# CM_ETHERNET.net
KiCad netlist of a schematic drawn in Altium Designer
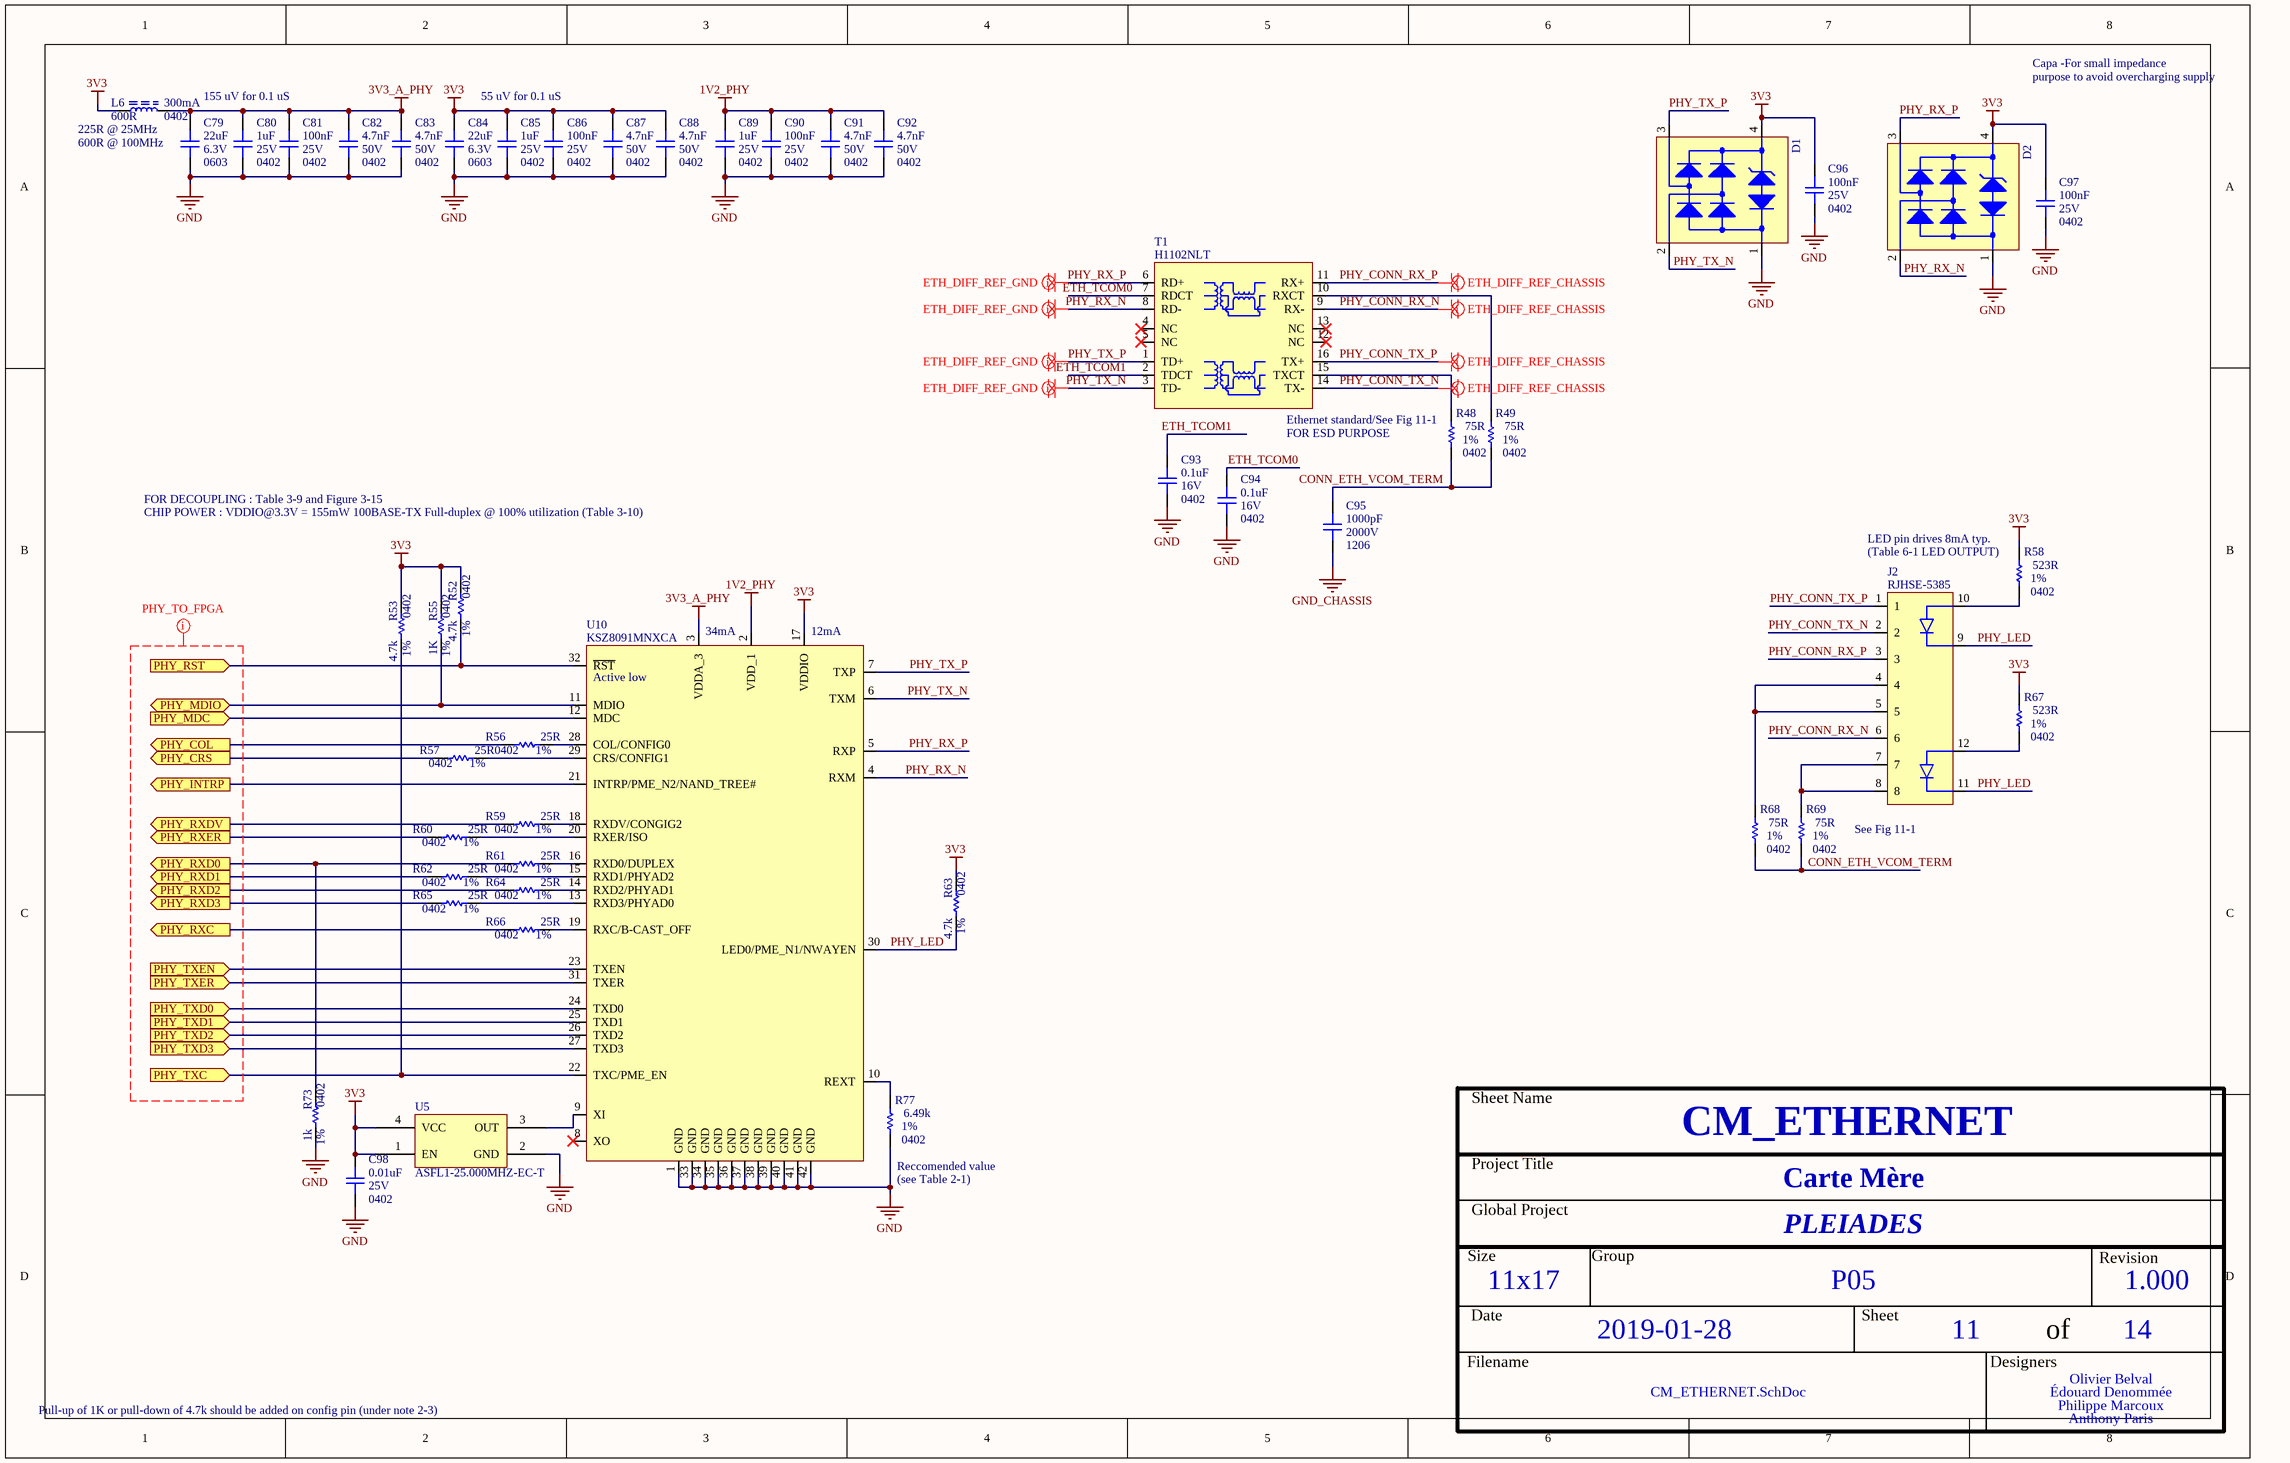
[diagram p0: CM_ETHERNET.SchDoc]

(export (version "E")
  (design (tool "Eeschema 10.0.6"))
  (components
    (comp (ref "C79")
      (value "22uF")
      (footprint "CAP_0603")
      (description "CAP - 0603")
      (fields
        (field (name "VOLTAGE") "6.3V")
        (field (name "PACKAGE") "0603")
        (field (name "CREATEDBY") "Jonathan Bouchard")
      )
      (libsource (lib "S7CAS_Lib2019_REV1_00") (part "CAP - 0603"))
    )
    (comp (ref "C80")
      (value "1uF")
      (footprint "CAP_0402")
      (description "CAP - 0402")
      (fields
        (field (name "VOLTAGE") "25V")
        (field (name "PACKAGE") "0402")
        (field (name "CREATEDBY") "Jonathan Bouchard")
      )
      (libsource (lib "S7CAS_Lib2019_REV1_00") (part "CAP - 0402"))
    )
    (comp (ref "C81")
      (value "100nF")
      (footprint "CAP_0402")
      (description "CAP - 0402")
      (fields
        (field (name "VOLTAGE") "25V")
        (field (name "PACKAGE") "0402")
        (field (name "CREATEDBY") "Jonathan Bouchard")
      )
      (libsource (lib "S7CAS_Lib2019_REV1_00") (part "CAP - 0402"))
    )
    (comp (ref "C82")
      (value "4.7nF")
      (footprint "CAP_0402")
      (description "CAP - 0402")
      (fields
        (field (name "VOLTAGE") "50V")
        (field (name "PACKAGE") "0402")
        (field (name "CREATEDBY") "Jonathan Bouchard")
      )
      (libsource (lib "S7CAS_Lib2019_REV1_00") (part "CAP - 0402"))
    )
    (comp (ref "C83")
      (value "4.7nF")
      (footprint "CAP_0402")
      (description "CAP - 0402")
      (fields
        (field (name "VOLTAGE") "50V")
        (field (name "PACKAGE") "0402")
        (field (name "CREATEDBY") "Jonathan Bouchard")
      )
      (libsource (lib "S7CAS_Lib2019_REV1_00") (part "CAP - 0402"))
    )
    (comp (ref "C84")
      (value "22uF")
      (footprint "CAP_0603")
      (description "CAP - 0603")
      (fields
        (field (name "VOLTAGE") "6.3V")
        (field (name "PACKAGE") "0603")
        (field (name "CREATEDBY") "Jonathan Bouchard")
      )
      (libsource (lib "S7CAS_Lib2019_REV1_00") (part "CAP - 0603"))
    )
    (comp (ref "C85")
      (value "1uF")
      (footprint "CAP_0402")
      (description "CAP - 0402")
      (fields
        (field (name "VOLTAGE") "25V")
        (field (name "PACKAGE") "0402")
        (field (name "CREATEDBY") "Jonathan Bouchard")
      )
      (libsource (lib "S7CAS_Lib2019_REV1_00") (part "CAP - 0402"))
    )
    (comp (ref "C86")
      (value "100nF")
      (footprint "CAP_0402")
      (description "CAP - 0402")
      (fields
        (field (name "VOLTAGE") "25V")
        (field (name "PACKAGE") "0402")
        (field (name "CREATEDBY") "Jonathan Bouchard")
      )
      (libsource (lib "S7CAS_Lib2019_REV1_00") (part "CAP - 0402"))
    )
    (comp (ref "C87")
      (value "4.7nF")
      (footprint "CAP_0402")
      (description "CAP - 0402")
      (fields
        (field (name "VOLTAGE") "50V")
        (field (name "PACKAGE") "0402")
        (field (name "CREATEDBY") "Jonathan Bouchard")
      )
      (libsource (lib "S7CAS_Lib2019_REV1_00") (part "CAP - 0402"))
    )
    (comp (ref "C88")
      (value "4.7nF")
      (footprint "CAP_0402")
      (description "CAP - 0402")
      (fields
        (field (name "VOLTAGE") "50V")
        (field (name "PACKAGE") "0402")
        (field (name "CREATEDBY") "Jonathan Bouchard")
      )
      (libsource (lib "S7CAS_Lib2019_REV1_00") (part "CAP - 0402"))
    )
    (comp (ref "C89")
      (value "1uF")
      (footprint "CAP_0402")
      (description "CAP - 0402")
      (fields
        (field (name "VOLTAGE") "25V")
        (field (name "PACKAGE") "0402")
        (field (name "CREATEDBY") "Jonathan Bouchard")
      )
      (libsource (lib "S7CAS_Lib2019_REV1_00") (part "CAP - 0402"))
    )
    (comp (ref "C90")
      (value "100nF")
      (footprint "CAP_0402")
      (description "CAP - 0402")
      (fields
        (field (name "VOLTAGE") "25V")
        (field (name "PACKAGE") "0402")
        (field (name "CREATEDBY") "Jonathan Bouchard")
      )
      (libsource (lib "S7CAS_Lib2019_REV1_00") (part "CAP - 0402"))
    )
    (comp (ref "C91")
      (value "4.7nF")
      (footprint "CAP_0402")
      (description "CAP - 0402")
      (fields
        (field (name "VOLTAGE") "50V")
        (field (name "PACKAGE") "0402")
        (field (name "CREATEDBY") "Jonathan Bouchard")
      )
      (libsource (lib "S7CAS_Lib2019_REV1_00") (part "CAP - 0402"))
    )
    (comp (ref "C92")
      (value "4.7nF")
      (footprint "CAP_0402")
      (description "CAP - 0402")
      (fields
        (field (name "VOLTAGE") "50V")
        (field (name "PACKAGE") "0402")
        (field (name "CREATEDBY") "Jonathan Bouchard")
      )
      (libsource (lib "S7CAS_Lib2019_REV1_00") (part "CAP - 0402"))
    )
    (comp (ref "C93")
      (value "0.1uF")
      (footprint "CAP_0402")
      (description "CAP - 0402")
      (fields
        (field (name "VOLTAGE") "16V")
        (field (name "PACKAGE") "0402")
        (field (name "CREATEDBY") "Jonathan Bouchard")
      )
      (libsource (lib "S7CAS_Lib2019_REV1_00") (part "CAP - 0402"))
    )
    (comp (ref "C94")
      (value "0.1uF")
      (footprint "CAP_0402")
      (description "CAP - 0402")
      (fields
        (field (name "VOLTAGE") "16V")
        (field (name "PACKAGE") "0402")
        (field (name "CREATEDBY") "Jonathan Bouchard")
      )
      (libsource (lib "S7CAS_Lib2019_REV1_00") (part "CAP - 0402"))
    )
    (comp (ref "C95")
      (value "1000pF")
      (footprint "CAP_1206")
      (description "CAP - 1206")
      (fields
        (field (name "VOLTAGE") "2000V")
        (field (name "PACKAGE") "1206")
        (field (name "CREATEDBY") "Jonathan Bouchard")
      )
      (libsource (lib "S7CAS_Lib2019_REV1_00") (part "CAP - 1206"))
    )
    (comp (ref "C96")
      (value "100nF")
      (footprint "CAP_0402")
      (description "CAP - 0402")
      (fields
        (field (name "VOLTAGE") "25V")
        (field (name "PACKAGE") "0402")
        (field (name "CREATEDBY") "Jonathan Bouchard")
      )
      (libsource (lib "S7CAS_Lib2019_REV1_00") (part "CAP - 0402"))
    )
    (comp (ref "C97")
      (value "100nF")
      (footprint "CAP_0402")
      (description "CAP - 0402")
      (fields
        (field (name "VOLTAGE") "25V")
        (field (name "PACKAGE") "0402")
        (field (name "CREATEDBY") "Jonathan Bouchard")
      )
      (libsource (lib "S7CAS_Lib2019_REV1_00") (part "CAP - 0402"))
    )
    (comp (ref "C98")
      (value "0.01uF")
      (footprint "CAP_0402")
      (description "CAP - 0402")
      (fields
        (field (name "VOLTAGE") "25V")
        (field (name "PACKAGE") "0402")
        (field (name "CREATEDBY") "Jonathan Bouchard")
      )
      (libsource (lib "S7CAS_Lib2019_REV1_00") (part "CAP - 0402"))
    )
    (comp (ref "D1")
      (value "SR3.3.TCT")
      (footprint "TVS_SR3.3.TCT")
      (description "TVS - DIODE ARRAY 3.3V 150W - SOT143-4")
      (fields
        (field (name "MFG") "Semtech")
        (field (name "POWER") "150W")
        (field (name "CREATEDBY") "Jonathan Bouchard")
      )
      (libsource (lib "S7CAS_Lib2019_REV1_00") (part "TVS_SR3.3.TCT"))
    )
    (comp (ref "D2")
      (value "SR3.3.TCT")
      (footprint "TVS_SR3.3.TCT")
      (description "TVS - DIODE ARRAY 3.3V 150W - SOT143-4")
      (fields
        (field (name "MFG") "Semtech")
        (field (name "POWER") "150W")
        (field (name "CREATEDBY") "Jonathan Bouchard")
      )
      (libsource (lib "S7CAS_Lib2019_REV1_00") (part "TVS_SR3.3.TCT"))
    )
    (comp (ref "J2")
      (value "RJHSE-5385")
      (footprint "CONN_ETHERNET_RJHSE-5385")
      (description "CONN - MOD JACK RJ45 R/A ETHERNET - TH")
      (fields (field (name "MFG") "Amphenol") (field (name "CREATEDBY") "Jonathan Bouchard"))
      (libsource (lib "S7CAS_Lib2019_REV1_00") (part "CONN_ETHERNET_RJHSE-5385"))
    )
    (comp (ref "L6")
      (value "600R")
      (footprint "FER_0402")
      (description "FER - 0402")
      (fields
        (field (name "CURRENT") "300mA")
        (field (name "PACKAGE") "0402")
        (field (name "CREATEDBY") "Jonathan Bouchard")
      )
      (libsource (lib "S7CAS_Lib2019_REV1_00") (part "FER - 0402"))
    )
    (comp (ref "R48")
      (value "75R")
      (footprint "RES_0402")
      (description "RES - 0402")
      (fields
        (field (name "VOLTAGE") "50V")
        (field (name "POWER") "1/16W")
        (field (name "PACKAGE") "0402")
        (field (name "PRECISION") "1%")
        (field (name "CREATEDBY") "Jonathan Bouchard")
      )
      (libsource (lib "S7CAS_Lib2019_REV1_00") (part "RES - 0402"))
    )
    (comp (ref "R49")
      (value "75R")
      (footprint "RES_0402")
      (description "RES - 0402")
      (fields
        (field (name "VOLTAGE") "50V")
        (field (name "POWER") "1/16W")
        (field (name "PACKAGE") "0402")
        (field (name "PRECISION") "1%")
        (field (name "CREATEDBY") "Jonathan Bouchard")
      )
      (libsource (lib "S7CAS_Lib2019_REV1_00") (part "RES - 0402"))
    )
    (comp (ref "R52")
      (value "4.7k")
      (footprint "RES_0402")
      (description "RES - 0402")
      (fields
        (field (name "VOLTAGE") "50V")
        (field (name "POWER") "1/16W")
        (field (name "PACKAGE") "0402")
        (field (name "PRECISION") "1%")
        (field (name "CREATEDBY") "Jonathan Bouchard")
      )
      (libsource (lib "S7CAS_Lib2019_REV1_00") (part "RES - 0402"))
    )
    (comp (ref "R53")
      (value "4.7k")
      (footprint "RES_0402")
      (description "RES - 0402")
      (fields
        (field (name "VOLTAGE") "50V")
        (field (name "POWER") "1/16W")
        (field (name "PACKAGE") "0402")
        (field (name "PRECISION") "1%")
        (field (name "CREATEDBY") "Jonathan Bouchard")
      )
      (libsource (lib "S7CAS_Lib2019_REV1_00") (part "RES - 0402"))
    )
    (comp (ref "R55")
      (value "1K")
      (footprint "RES_0402")
      (description "RES - 0402")
      (fields
        (field (name "VOLTAGE") "50V")
        (field (name "POWER") "1/16W")
        (field (name "PACKAGE") "0402")
        (field (name "PRECISION") "1%")
        (field (name "CREATEDBY") "Jonathan Bouchard")
      )
      (libsource (lib "S7CAS_Lib2019_REV1_00") (part "RES - 0402"))
    )
    (comp (ref "R56")
      (value "25R")
      (footprint "RES_0402")
      (description "RES - 0402")
      (fields
        (field (name "VOLTAGE") "50V")
        (field (name "POWER") "1/16W")
        (field (name "PACKAGE") "0402")
        (field (name "PRECISION") "1%")
        (field (name "CREATEDBY") "Jonathan Bouchard")
      )
      (libsource (lib "S7CAS_Lib2019_REV1_00") (part "RES - 0402"))
    )
    (comp (ref "R57")
      (value "25R")
      (footprint "RES_0402")
      (description "RES - 0402")
      (fields
        (field (name "VOLTAGE") "50V")
        (field (name "POWER") "1/16W")
        (field (name "PACKAGE") "0402")
        (field (name "PRECISION") "1%")
        (field (name "CREATEDBY") "Jonathan Bouchard")
      )
      (libsource (lib "S7CAS_Lib2019_REV1_00") (part "RES - 0402"))
    )
    (comp (ref "R58")
      (value "523R")
      (footprint "RES_0402")
      (description "RES - 0402")
      (fields
        (field (name "VOLTAGE") "50V")
        (field (name "POWER") "1/16W")
        (field (name "PACKAGE") "0402")
        (field (name "PRECISION") "1%")
        (field (name "CREATEDBY") "Jonathan Bouchard")
      )
      (libsource (lib "S7CAS_Lib2019_REV1_00") (part "RES - 0402"))
    )
    (comp (ref "R59")
      (value "25R")
      (footprint "RES_0402")
      (description "RES - 0402")
      (fields
        (field (name "VOLTAGE") "50V")
        (field (name "POWER") "1/16W")
        (field (name "PACKAGE") "0402")
        (field (name "PRECISION") "1%")
        (field (name "CREATEDBY") "Jonathan Bouchard")
      )
      (libsource (lib "S7CAS_Lib2019_REV1_00") (part "RES - 0402"))
    )
    (comp (ref "R60")
      (value "25R")
      (footprint "RES_0402")
      (description "RES - 0402")
      (fields
        (field (name "VOLTAGE") "50V")
        (field (name "POWER") "1/16W")
        (field (name "PACKAGE") "0402")
        (field (name "PRECISION") "1%")
        (field (name "CREATEDBY") "Jonathan Bouchard")
      )
      (libsource (lib "S7CAS_Lib2019_REV1_00") (part "RES - 0402"))
    )
    (comp (ref "R61")
      (value "25R")
      (footprint "RES_0402")
      (description "RES - 0402")
      (fields
        (field (name "VOLTAGE") "50V")
        (field (name "POWER") "1/16W")
        (field (name "PACKAGE") "0402")
        (field (name "PRECISION") "1%")
        (field (name "CREATEDBY") "Jonathan Bouchard")
      )
      (libsource (lib "S7CAS_Lib2019_REV1_00") (part "RES - 0402"))
    )
    (comp (ref "R62")
      (value "25R")
      (footprint "RES_0402")
      (description "RES - 0402")
      (fields
        (field (name "VOLTAGE") "50V")
        (field (name "POWER") "1/16W")
        (field (name "PACKAGE") "0402")
        (field (name "PRECISION") "1%")
        (field (name "CREATEDBY") "Jonathan Bouchard")
      )
      (libsource (lib "S7CAS_Lib2019_REV1_00") (part "RES - 0402"))
    )
    (comp (ref "R63")
      (value "4.7k")
      (footprint "RES_0402")
      (description "RES - 0402")
      (fields
        (field (name "VOLTAGE") "50V")
        (field (name "POWER") "1/16W")
        (field (name "PACKAGE") "0402")
        (field (name "PRECISION") "1%")
        (field (name "CREATEDBY") "Jonathan Bouchard")
      )
      (libsource (lib "S7CAS_Lib2019_REV1_00") (part "RES - 0402"))
    )
    (comp (ref "R64")
      (value "25R")
      (footprint "RES_0402")
      (description "RES - 0402")
      (fields
        (field (name "VOLTAGE") "50V")
        (field (name "POWER") "1/16W")
        (field (name "PACKAGE") "0402")
        (field (name "PRECISION") "1%")
        (field (name "CREATEDBY") "Jonathan Bouchard")
      )
      (libsource (lib "S7CAS_Lib2019_REV1_00") (part "RES - 0402"))
    )
    (comp (ref "R65")
      (value "25R")
      (footprint "RES_0402")
      (description "RES - 0402")
      (fields
        (field (name "VOLTAGE") "50V")
        (field (name "POWER") "1/16W")
        (field (name "PACKAGE") "0402")
        (field (name "PRECISION") "1%")
        (field (name "CREATEDBY") "Jonathan Bouchard")
      )
      (libsource (lib "S7CAS_Lib2019_REV1_00") (part "RES - 0402"))
    )
    (comp (ref "R66")
      (value "25R")
      (footprint "RES_0402")
      (description "RES - 0402")
      (fields
        (field (name "VOLTAGE") "50V")
        (field (name "POWER") "1/16W")
        (field (name "PACKAGE") "0402")
        (field (name "PRECISION") "1%")
        (field (name "CREATEDBY") "Jonathan Bouchard")
      )
      (libsource (lib "S7CAS_Lib2019_REV1_00") (part "RES - 0402"))
    )
    (comp (ref "R67")
      (value "523R")
      (footprint "RES_0402")
      (description "RES - 0402")
      (fields
        (field (name "VOLTAGE") "50V")
        (field (name "POWER") "1/16W")
        (field (name "PACKAGE") "0402")
        (field (name "PRECISION") "1%")
        (field (name "CREATEDBY") "Jonathan Bouchard")
      )
      (libsource (lib "S7CAS_Lib2019_REV1_00") (part "RES - 0402"))
    )
    (comp (ref "R68")
      (value "75R")
      (footprint "RES_0402")
      (description "RES - 0402")
      (fields
        (field (name "VOLTAGE") "50V")
        (field (name "POWER") "1/16W")
        (field (name "PACKAGE") "0402")
        (field (name "PRECISION") "1%")
        (field (name "CREATEDBY") "Jonathan Bouchard")
      )
      (libsource (lib "S7CAS_Lib2019_REV1_00") (part "RES - 0402"))
    )
    (comp (ref "R69")
      (value "75R")
      (footprint "RES_0402")
      (description "RES - 0402")
      (fields
        (field (name "VOLTAGE") "50V")
        (field (name "POWER") "1/16W")
        (field (name "PACKAGE") "0402")
        (field (name "PRECISION") "1%")
        (field (name "CREATEDBY") "Jonathan Bouchard")
      )
      (libsource (lib "S7CAS_Lib2019_REV1_00") (part "RES - 0402"))
    )
    (comp (ref "R73")
      (value "1k")
      (footprint "RES_0402")
      (description "RES - 0402")
      (fields
        (field (name "VOLTAGE") "50V")
        (field (name "POWER") "1/16W")
        (field (name "PACKAGE") "0402")
        (field (name "PRECISION") "1%")
        (field (name "CREATEDBY") "Jonathan Bouchard")
      )
      (libsource (lib "S7CAS_Lib2019_REV1_00") (part "RES - 0402"))
    )
    (comp (ref "R77")
      (value "6.49k")
      (footprint "RES_0402")
      (description "RES - 0402")
      (fields
        (field (name "VOLTAGE") "50V")
        (field (name "POWER") "1/16W")
        (field (name "PACKAGE") "0402")
        (field (name "PRECISION") "1%")
        (field (name "CREATEDBY") "Jonathan Bouchard")
      )
      (libsource (lib "S7CAS_Lib2019_REV1_00") (part "RES - 0402"))
    )
    (comp (ref "T1")
      (value "H1102NLT")
      (footprint "TRANSFO_H1102NLT")
      (description "TRANSFO - ETHERNET 10/100B-TX - SMD-16")
      (fields (field (name "MFG") "Pulse Eng.") (field (name "CREATEDBY") "Jonathan Bouchard"))
      (libsource (lib "S7CAS_Lib2019_REV1_00") (part "TRANSFO_H1102NLT"))
    )
    (comp (ref "U5")
      (value "ASFL1-25.000MHZ-EC-T")
      (footprint "ASFL1")
      (libsource (lib "OSC_25MHZ") (part "ASFL1-25.000MHZ-EC-T"))
    )
    (comp (ref "U10")
      (value "KSZ8091MNXCA")
      (footprint "COM_ETH_PHY_KSZ8091MNXCA")
      (description "COM - ETHERNET PHY 10/100 - QFN-32")
      (fields
        (field (name "VOLTAGE") "1.8V, 2.5V, 3.3V")
        (field (name "MFG") "Micrel")
        (field (name "CREATEDBY") "Jonathan Bouchard")
      )
      (libsource (lib "S7CAS_Lib2019_REV1_00") (part "COM_ETH_PHY_KSZ8091MNXCA"))
    )
  )
  (nets
    (net (code "1") (name "/CONN_ETH_VCOM_TERM") (class "Default")
      (node (ref "C95") (pin "2") (pinfunction "2_2") (pintype "passive"))
      (node (ref "R48") (pin "1") (pinfunction "1_1") (pintype "passive"))
      (node (ref "R49") (pin "1") (pinfunction "1_1") (pintype "passive"))
      (node (ref "R68") (pin "1") (pinfunction "1_1") (pintype "passive"))
      (node (ref "R69") (pin "1") (pinfunction "1_1") (pintype "passive"))
    )
    (net (code "2") (name "/ETH_TCOM0") (class "Default")
      (node (ref "C94") (pin "2") (pinfunction "2_2") (pintype "passive"))
      (node (ref "T1") (pin "7") (pinfunction "RDCT_7") (pintype "passive"))
    )
    (net (code "3") (name "/ETH_TCOM1") (class "Default")
      (node (ref "C93") (pin "2") (pinfunction "2_2") (pintype "passive"))
      (node (ref "T1") (pin "2") (pinfunction "TDCT_2") (pintype "passive"))
    )
    (net (code "4") (name "/PHY_COL") (class "Default")
      (node (ref "R56") (pin "2") (pinfunction "2_2") (pintype "passive"))
    )
    (net (code "5") (name "/PHY_CONN_RX_N") (class "Default")
      (node (ref "J2") (pin "6") (pinfunction "6_6") (pintype "passive"))
      (node (ref "T1") (pin "9") (pinfunction "RX-_9") (pintype "passive"))
    )
    (net (code "6") (name "/PHY_CONN_RX_P") (class "Default")
      (node (ref "J2") (pin "3") (pinfunction "3_3") (pintype "passive"))
      (node (ref "T1") (pin "11") (pinfunction "RX+_11") (pintype "passive"))
    )
    (net (code "7") (name "/PHY_CONN_TX_N") (class "Default")
      (node (ref "J2") (pin "2") (pinfunction "2_2") (pintype "passive"))
      (node (ref "T1") (pin "14") (pinfunction "TX-_14") (pintype "passive"))
    )
    (net (code "8") (name "/PHY_CONN_TX_P") (class "Default")
      (node (ref "J2") (pin "1") (pinfunction "1_1") (pintype "passive"))
      (node (ref "T1") (pin "16") (pinfunction "TX+_16") (pintype "passive"))
    )
    (net (code "9") (name "/PHY_CRS") (class "Default")
      (node (ref "R57") (pin "2") (pinfunction "2_2") (pintype "passive"))
    )
    (net (code "10") (name "/PHY_INTRP") (class "Default")
      (node (ref "U10") (pin "21") (pinfunction "INTRP/PME_N2/NAND_TREE#_21") (pintype "passive"))
    )
    (net (code "11") (name "/PHY_LED") (class "Default")
      (node (ref "J2") (pin "11") (pinfunction "LED2_K_11") (pintype "passive"))
      (node (ref "J2") (pin "9") (pinfunction "LED1_K_9") (pintype "passive"))
      (node (ref "R63") (pin "1") (pinfunction "1_1") (pintype "passive"))
      (node (ref "U10") (pin "30") (pinfunction "LED0/PME_N1/NWAYEN_30") (pintype "passive"))
    )
    (net (code "12") (name "/PHY_MDC") (class "Default")
      (node (ref "U10") (pin "12") (pinfunction "MDC_12") (pintype "passive"))
    )
    (net (code "13") (name "/PHY_MDIO") (class "Default")
      (node (ref "R55") (pin "1") (pinfunction "1_1") (pintype "passive"))
      (node (ref "U10") (pin "11") (pinfunction "MDIO_11") (pintype "passive"))
    )
    (net (code "14") (name "/PHY_RST") (class "Default")
      (node (ref "R52") (pin "1") (pinfunction "1_1") (pintype "passive"))
      (node (ref "U10") (pin "32") (pinfunction "RST_32") (pintype "passive"))
    )
    (net (code "15") (name "/PHY_RXC") (class "Default")
      (node (ref "R66") (pin "2") (pinfunction "2_2") (pintype "passive"))
    )
    (net (code "16") (name "/PHY_RXD0") (class "Default")
      (node (ref "R61") (pin "2") (pinfunction "2_2") (pintype "passive"))
      (node (ref "R73") (pin "2") (pinfunction "2_2") (pintype "passive"))
    )
    (net (code "17") (name "/PHY_RXD1") (class "Default")
      (node (ref "R62") (pin "2") (pinfunction "2_2") (pintype "passive"))
    )
    (net (code "18") (name "/PHY_RXD2") (class "Default")
      (node (ref "R64") (pin "2") (pinfunction "2_2") (pintype "passive"))
    )
    (net (code "19") (name "/PHY_RXD3") (class "Default")
      (node (ref "R65") (pin "2") (pinfunction "2_2") (pintype "passive"))
    )
    (net (code "20") (name "/PHY_RXDV") (class "Default")
      (node (ref "R59") (pin "2") (pinfunction "2_2") (pintype "passive"))
    )
    (net (code "21") (name "/PHY_RXER") (class "Default")
      (node (ref "R60") (pin "2") (pinfunction "2_2") (pintype "passive"))
    )
    (net (code "22") (name "/PHY_RX_N") (class "Default")
      (node (ref "D2") (pin "2") (pinfunction "VN_2") (pintype "passive"))
      (node (ref "T1") (pin "8") (pinfunction "RD-_8") (pintype "passive"))
      (node (ref "U10") (pin "4") (pinfunction "RXM_4") (pintype "passive"))
    )
    (net (code "23") (name "/PHY_RX_P") (class "Default")
      (node (ref "D2") (pin "3") (pintype "passive"))
      (node (ref "T1") (pin "6") (pinfunction "RD+_6") (pintype "passive"))
      (node (ref "U10") (pin "5") (pinfunction "RXP_5") (pintype "passive"))
    )
    (net (code "24") (name "/PHY_TXC") (class "Default")
      (node (ref "R53") (pin "1") (pinfunction "1_1") (pintype "passive"))
      (node (ref "U10") (pin "22") (pinfunction "TXC/PME_EN_22") (pintype "passive"))
    )
    (net (code "25") (name "/PHY_TXD0") (class "Default")
      (node (ref "U10") (pin "24") (pinfunction "TXD0_24") (pintype "passive"))
    )
    (net (code "26") (name "/PHY_TXD1") (class "Default")
      (node (ref "U10") (pin "25") (pinfunction "TXD1_25") (pintype "passive"))
    )
    (net (code "27") (name "/PHY_TXD2") (class "Default")
      (node (ref "U10") (pin "26") (pinfunction "TXD2_26") (pintype "passive"))
    )
    (net (code "28") (name "/PHY_TXD3") (class "Default")
      (node (ref "U10") (pin "27") (pinfunction "TXD3_27") (pintype "passive"))
    )
    (net (code "29") (name "/PHY_TXEN") (class "Default")
      (node (ref "U10") (pin "23") (pinfunction "TXEN_23") (pintype "passive"))
    )
    (net (code "30") (name "/PHY_TXER") (class "Default")
      (node (ref "U10") (pin "31") (pinfunction "TXER_31") (pintype "passive"))
    )
    (net (code "31") (name "/PHY_TX_N") (class "Default")
      (node (ref "D1") (pin "2") (pinfunction "VN_2") (pintype "passive"))
      (node (ref "T1") (pin "3") (pinfunction "TD-_3") (pintype "passive"))
      (node (ref "U10") (pin "6") (pinfunction "TXM_6") (pintype "passive"))
    )
    (net (code "32") (name "/PHY_TX_P") (class "Default")
      (node (ref "D1") (pin "3") (pintype "passive"))
      (node (ref "T1") (pin "1") (pinfunction "TD+_1") (pintype "passive"))
      (node (ref "U10") (pin "7") (pinfunction "TXP_7") (pintype "passive"))
    )
    (net (code "33") (name "1V2_PHY") (class "Default")
      (node (ref "C89") (pin "2") (pinfunction "2_2") (pintype "passive"))
      (node (ref "C90") (pin "2") (pinfunction "2_2") (pintype "passive"))
      (node (ref "C91") (pin "2") (pinfunction "2_2") (pintype "passive"))
      (node (ref "C92") (pin "2") (pinfunction "2_2") (pintype "passive"))
      (node (ref "U10") (pin "2") (pinfunction "VDD_1_2") (pintype "power_in"))
    )
    (net (code "34") (name "3V3") (class "Default")
      (node (ref "C84") (pin "2") (pinfunction "2_2") (pintype "passive"))
      (node (ref "C85") (pin "2") (pinfunction "2_2") (pintype "passive"))
      (node (ref "C86") (pin "2") (pinfunction "2_2") (pintype "passive"))
      (node (ref "C87") (pin "2") (pinfunction "2_2") (pintype "passive"))
      (node (ref "C88") (pin "2") (pinfunction "2_2") (pintype "passive"))
      (node (ref "C96") (pin "2") (pinfunction "2_2") (pintype "passive"))
      (node (ref "C97") (pin "2") (pinfunction "2_2") (pintype "passive"))
      (node (ref "C98") (pin "2") (pinfunction "2_2") (pintype "passive"))
      (node (ref "D1") (pin "4") (pintype "passive"))
      (node (ref "D2") (pin "4") (pintype "passive"))
      (node (ref "L6") (pin "2") (pinfunction "2_2") (pintype "passive"))
      (node (ref "R52") (pin "2") (pinfunction "2_2") (pintype "passive"))
      (node (ref "R53") (pin "2") (pinfunction "2_2") (pintype "passive"))
      (node (ref "R55") (pin "2") (pinfunction "2_2") (pintype "passive"))
      (node (ref "R58") (pin "2") (pinfunction "2_2") (pintype "passive"))
      (node (ref "R63") (pin "2") (pinfunction "2_2") (pintype "passive"))
      (node (ref "R67") (pin "2") (pinfunction "2_2") (pintype "passive"))
      (node (ref "U10") (pin "17") (pinfunction "VDDIO_17") (pintype "power_in"))
      (node (ref "U5") (pin "1") (pinfunction "EN_1") (pintype "passive"))
      (node (ref "U5") (pin "4") (pinfunction "VCC_4") (pintype "passive"))
    )
    (net (code "35") (name "3V3_A_PHY") (class "Default")
      (node (ref "C79") (pin "2") (pinfunction "2_2") (pintype "passive"))
      (node (ref "C80") (pin "2") (pinfunction "2_2") (pintype "passive"))
      (node (ref "C81") (pin "2") (pinfunction "2_2") (pintype "passive"))
      (node (ref "C82") (pin "2") (pinfunction "2_2") (pintype "passive"))
      (node (ref "C83") (pin "2") (pinfunction "2_2") (pintype "passive"))
      (node (ref "L6") (pin "1") (pinfunction "1_1") (pintype "passive"))
      (node (ref "U10") (pin "3") (pinfunction "VDDA_3_3") (pintype "power_in"))
    )
    (net (code "36") (name "GND") (class "Default")
      (node (ref "C79") (pin "1") (pinfunction "1_1") (pintype "passive"))
      (node (ref "C80") (pin "1") (pinfunction "1_1") (pintype "passive"))
      (node (ref "C81") (pin "1") (pinfunction "1_1") (pintype "passive"))
      (node (ref "C82") (pin "1") (pinfunction "1_1") (pintype "passive"))
      (node (ref "C83") (pin "1") (pinfunction "1_1") (pintype "passive"))
      (node (ref "C84") (pin "1") (pinfunction "1_1") (pintype "passive"))
      (node (ref "C85") (pin "1") (pinfunction "1_1") (pintype "passive"))
      (node (ref "C86") (pin "1") (pinfunction "1_1") (pintype "passive"))
      (node (ref "C87") (pin "1") (pinfunction "1_1") (pintype "passive"))
      (node (ref "C88") (pin "1") (pinfunction "1_1") (pintype "passive"))
      (node (ref "C89") (pin "1") (pinfunction "1_1") (pintype "passive"))
      (node (ref "C90") (pin "1") (pinfunction "1_1") (pintype "passive"))
      (node (ref "C91") (pin "1") (pinfunction "1_1") (pintype "passive"))
      (node (ref "C92") (pin "1") (pinfunction "1_1") (pintype "passive"))
      (node (ref "C93") (pin "1") (pinfunction "1_1") (pintype "passive"))
      (node (ref "C94") (pin "1") (pinfunction "1_1") (pintype "passive"))
      (node (ref "C96") (pin "1") (pinfunction "1_1") (pintype "passive"))
      (node (ref "C97") (pin "1") (pinfunction "1_1") (pintype "passive"))
      (node (ref "C98") (pin "1") (pinfunction "1_1") (pintype "passive"))
      (node (ref "D1") (pin "1") (pinfunction "I/O_1") (pintype "passive"))
      (node (ref "D2") (pin "1") (pinfunction "I/O_1") (pintype "passive"))
      (node (ref "R73") (pin "1") (pinfunction "1_1") (pintype "passive"))
      (node (ref "R77") (pin "1") (pinfunction "1_1") (pintype "passive"))
      (node (ref "U10") (pin "1") (pinfunction "GND_1") (pintype "passive"))
      (node (ref "U10") (pin "33") (pinfunction "GND_33") (pintype "passive"))
      (node (ref "U10") (pin "34") (pinfunction "GND_34") (pintype "passive"))
      (node (ref "U10") (pin "35") (pinfunction "GND_35") (pintype "passive"))
      (node (ref "U10") (pin "36") (pinfunction "GND_36") (pintype "passive"))
      (node (ref "U10") (pin "37") (pinfunction "GND_37") (pintype "passive"))
      (node (ref "U10") (pin "38") (pinfunction "GND_38") (pintype "passive"))
      (node (ref "U10") (pin "39") (pinfunction "GND_39") (pintype "passive"))
      (node (ref "U10") (pin "40") (pinfunction "GND_40") (pintype "passive"))
      (node (ref "U10") (pin "41") (pinfunction "GND_41") (pintype "passive"))
      (node (ref "U10") (pin "42") (pinfunction "GND_42") (pintype "passive"))
      (node (ref "U5") (pin "2") (pinfunction "GND_2") (pintype "passive"))
    )
    (net (code "37") (name "GND_CHASSIS") (class "Default")
      (node (ref "C95") (pin "1") (pinfunction "1_1") (pintype "passive"))
    )
    (net (code "38") (name "Net-(J2-LED1_A)") (class "Default")
      (node (ref "J2") (pin "10") (pinfunction "LED1_A_10") (pintype "passive"))
      (node (ref "R58") (pin "1") (pinfunction "1_1") (pintype "passive"))
    )
    (net (code "39") (name "Net-(J2-LED2_A)") (class "Default")
      (node (ref "J2") (pin "12") (pinfunction "LED2_A_12") (pintype "passive"))
      (node (ref "R67") (pin "1") (pinfunction "1_1") (pintype "passive"))
    )
    (net (code "40") (name "Net-(J2-Pad4)") (class "Default")
      (node (ref "J2") (pin "4") (pinfunction "4_4") (pintype "passive"))
      (node (ref "J2") (pin "5") (pinfunction "5_5") (pintype "passive"))
      (node (ref "R68") (pin "2") (pinfunction "2_2") (pintype "passive"))
    )
    (net (code "41") (name "Net-(J2-Pad7)") (class "Default")
      (node (ref "J2") (pin "7") (pinfunction "7_7") (pintype "passive"))
      (node (ref "J2") (pin "8") (pinfunction "8_8") (pintype "passive"))
      (node (ref "R69") (pin "2") (pinfunction "2_2") (pintype "passive"))
    )
    (net (code "42") (name "Net-(T1-RXCT)") (class "Default")
      (node (ref "R49") (pin "2") (pinfunction "2_2") (pintype "passive"))
      (node (ref "T1") (pin "10") (pinfunction "RXCT_10") (pintype "passive"))
    )
    (net (code "43") (name "Net-(T1-TXCT)") (class "Default")
      (node (ref "R48") (pin "2") (pinfunction "2_2") (pintype "passive"))
      (node (ref "T1") (pin "15") (pinfunction "TXCT_15") (pintype "passive"))
    )
    (net (code "44") (name "Net-(U10-COL{slash}CONFIG0)") (class "Default")
      (node (ref "R56") (pin "1") (pinfunction "1_1") (pintype "passive"))
      (node (ref "U10") (pin "28") (pinfunction "COL/CONFIG0_28") (pintype "passive"))
    )
    (net (code "45") (name "Net-(U10-CRS{slash}CONFIG1)") (class "Default")
      (node (ref "R57") (pin "1") (pinfunction "1_1") (pintype "passive"))
      (node (ref "U10") (pin "29") (pinfunction "CRS/CONFIG1_29") (pintype "passive"))
    )
    (net (code "46") (name "Net-(U10-REXT)") (class "Default")
      (node (ref "R77") (pin "2") (pinfunction "2_2") (pintype "passive"))
      (node (ref "U10") (pin "10") (pinfunction "REXT_10") (pintype "passive"))
    )
    (net (code "47") (name "Net-(U10-RXC{slash}B-CAST_OFF)") (class "Default")
      (node (ref "R66") (pin "1") (pinfunction "1_1") (pintype "passive"))
      (node (ref "U10") (pin "19") (pinfunction "RXC/B-CAST_OFF_19") (pintype "passive"))
    )
    (net (code "48") (name "Net-(U10-RXD0{slash}DUPLEX)") (class "Default")
      (node (ref "R61") (pin "1") (pinfunction "1_1") (pintype "passive"))
      (node (ref "U10") (pin "16") (pinfunction "RXD0/DUPLEX_16") (pintype "passive"))
    )
    (net (code "49") (name "Net-(U10-RXD1{slash}PHYAD2)") (class "Default")
      (node (ref "R62") (pin "1") (pinfunction "1_1") (pintype "passive"))
      (node (ref "U10") (pin "15") (pinfunction "RXD1/PHYAD2_15") (pintype "passive"))
    )
    (net (code "50") (name "Net-(U10-RXD2{slash}PHYAD1)") (class "Default")
      (node (ref "R64") (pin "1") (pinfunction "1_1") (pintype "passive"))
      (node (ref "U10") (pin "14") (pinfunction "RXD2/PHYAD1_14") (pintype "passive"))
    )
    (net (code "51") (name "Net-(U10-RXD3{slash}PHYAD0)") (class "Default")
      (node (ref "R65") (pin "1") (pinfunction "1_1") (pintype "passive"))
      (node (ref "U10") (pin "13") (pinfunction "RXD3/PHYAD0_13") (pintype "passive"))
    )
    (net (code "52") (name "Net-(U10-RXDV{slash}CONGIG2)") (class "Default")
      (node (ref "R59") (pin "1") (pinfunction "1_1") (pintype "passive"))
      (node (ref "U10") (pin "18") (pinfunction "RXDV/CONGIG2_18") (pintype "passive"))
    )
    (net (code "53") (name "Net-(U10-RXER{slash}ISO)") (class "Default")
      (node (ref "R60") (pin "1") (pinfunction "1_1") (pintype "passive"))
      (node (ref "U10") (pin "20") (pinfunction "RXER/ISO_20") (pintype "passive"))
    )
    (net (code "54") (name "Net-(U10-XI)") (class "Default")
      (node (ref "U10") (pin "9") (pinfunction "XI_9") (pintype "passive"))
      (node (ref "U5") (pin "3") (pinfunction "OUT_3") (pintype "passive"))
    )
    (net (code "55") (name "unconnected-(T1-NC-Pad4)") (class "Default")
      (node (ref "T1") (pin "4") (pinfunction "NC_4") (pintype "passive+no_connect"))
    )
    (net (code "56") (name "unconnected-(T1-NC-Pad5)") (class "Default")
      (node (ref "T1") (pin "5") (pinfunction "NC_5") (pintype "passive+no_connect"))
    )
    (net (code "57") (name "unconnected-(T1-NC-Pad12)") (class "Default")
      (node (ref "T1") (pin "12") (pinfunction "NC_12") (pintype "passive+no_connect"))
    )
    (net (code "58") (name "unconnected-(T1-NC-Pad13)") (class "Default")
      (node (ref "T1") (pin "13") (pinfunction "NC_13") (pintype "passive+no_connect"))
    )
    (net (code "59") (name "unconnected-(U10-XO-Pad8)") (class "Default")
      (node (ref "U10") (pin "8") (pinfunction "XO_8") (pintype "passive+no_connect"))
    )
  )
)
